# 08-RF_GPS.net
KiCad netlist of a schematic drawn in Altium Designer
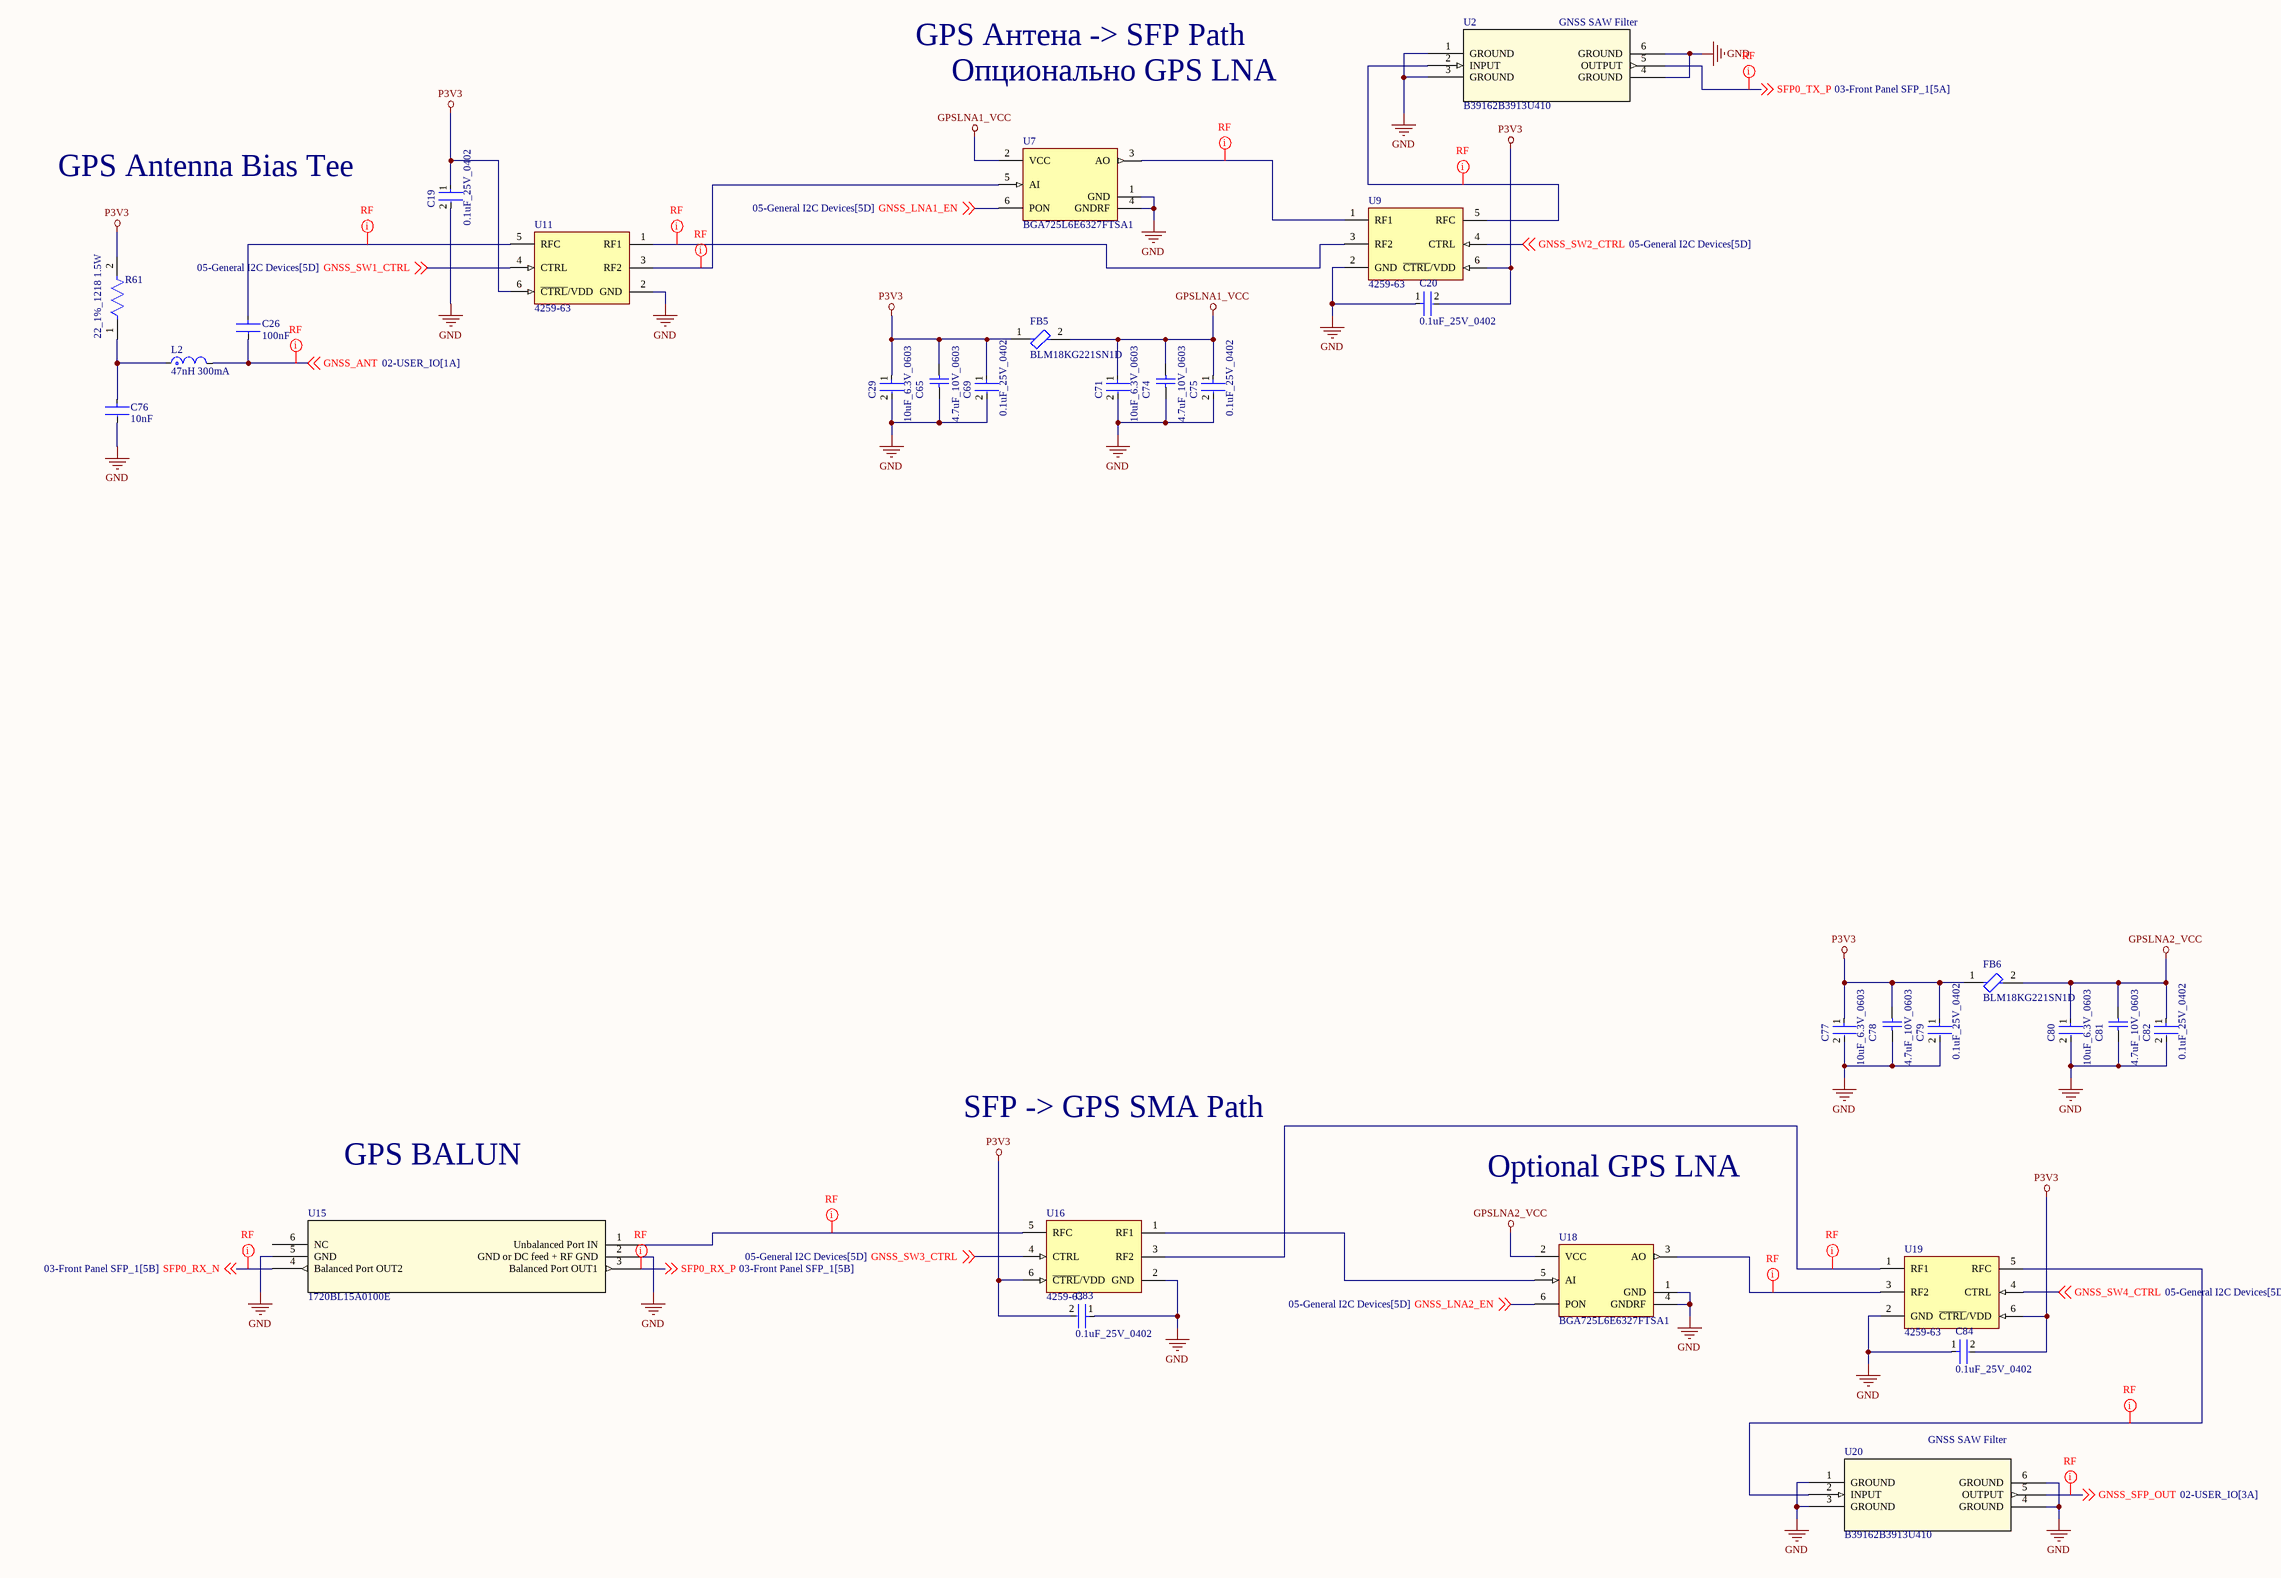
[diagram p0: 08-RF_GPS.SchDoc]

(export (version "E")
  (design (tool "Eeschema 10.0.6"))
  (components
    (comp (ref "C19")
      (value "0.1uF_25V_0402")
      (footprint "FP-0402-L_1_0_1-W_0_5_0_1-IPC_C")
      (description "General Purpose Ceramic Capacitor, 0402, 100nF, 10%, X7R, 15%, 25V")
      (fields (field (name "VOLTAGE") "25V") (field (name "TOLERANCE") "10%"))
      (libsource (lib "Altium Content Vault") (part "b4654b650e69147ec39a6b967a45e02"))
    )
    (comp (ref "C20")
      (value "0.1uF_25V_0402")
      (footprint "FP-0402-L_1_0_1-W_0_5_0_1-IPC_C")
      (description "General Purpose Ceramic Capacitor, 0402, 100nF, 10%, X7R, 15%, 25V")
      (fields (field (name "VOLTAGE") "25V") (field (name "TOLERANCE") "10%"))
      (libsource (lib "Altium Content Vault") (part "b4654b650e69147ec39a6b967a45e02"))
    )
    (comp (ref "C26")
      (value "100nF")
      (footprint "FP-0402-L_1_0_0_05-W_0_5-IPC_B")
      (description "None")
      (fields (field (name "TOLERANCE") "10%"))
      (libsource (lib "") (part "b4654b650e69147ec39a6b967a45e02_1"))
    )
    (comp (ref "C29")
      (value "10uF_6.3V_0603")
      (footprint "FP-C0603C106M9PACTU-MFG")
      (description "CAP CER 10UF 6.3V X5R 0603")
      (fields
        (field (name "MANUFACTURER PART NUMBER") "C0603C106M9PACTU")
        (field (name "MANUFACTURER") "Kemet")
      )
      (libsource (lib "Altium Content Vault") (part "b4654b650e69147ec39a6b967a45e02"))
    )
    (comp (ref "C65")
      (value "4.7uF_10V_0603")
      (footprint "CAPC1608X87X35NL15T15")
      (fields (field (name "PART NUMBER") "C0603C475K8PACTU") (field (name "MANUFACTURER") "Kemet"))
      (libsource (lib "Altium Content Vault") (part "CAP"))
    )
    (comp (ref "C69")
      (value "0.1uF_25V_0402")
      (footprint "FP-0402-L_1_0_1-W_0_5_0_1-IPC_C")
      (description "General Purpose Ceramic Capacitor, 0402, 100nF, 10%, X7R, 15%, 25V")
      (fields (field (name "VOLTAGE") "25V") (field (name "TOLERANCE") "10%"))
      (libsource (lib "Altium Content Vault") (part "b4654b650e69147ec39a6b967a45e02"))
    )
    (comp (ref "C71")
      (value "10uF_6.3V_0603")
      (footprint "FP-C0603C106M9PACTU-MFG")
      (description "CAP CER 10UF 6.3V X5R 0603")
      (fields
        (field (name "MANUFACTURER PART NUMBER") "C0603C106M9PACTU")
        (field (name "MANUFACTURER") "Kemet")
      )
      (libsource (lib "Altium Content Vault") (part "b4654b650e69147ec39a6b967a45e02"))
    )
    (comp (ref "C74")
      (value "4.7uF_10V_0603")
      (footprint "CAPC1608X87X35NL15T15")
      (fields (field (name "PART NUMBER") "C0603C475K8PACTU") (field (name "MANUFACTURER") "Kemet"))
      (libsource (lib "Altium Content Vault") (part "CAP"))
    )
    (comp (ref "C75")
      (value "0.1uF_25V_0402")
      (footprint "FP-0402-L_1_0_1-W_0_5_0_1-IPC_C")
      (description "General Purpose Ceramic Capacitor, 0402, 100nF, 10%, X7R, 15%, 25V")
      (fields (field (name "VOLTAGE") "25V") (field (name "TOLERANCE") "10%"))
      (libsource (lib "Altium Content Vault") (part "b4654b650e69147ec39a6b967a45e02"))
    )
    (comp (ref "C76")
      (value "10nF")
      (footprint "FP-GRM033-0_03-IPC_B")
      (description "Chip Multilayer Ceramic Capacitors for General Purpose, 0201, 10000pF, X7R, 15%, 10%, 16V")
      (fields (field (name "TOLERANCE") "10%"))
      (libsource (lib "") (part "b4654b650e69147ec39a6b967a45e02_1"))
    )
    (comp (ref "C77")
      (value "10uF_6.3V_0603")
      (footprint "FP-C0603C106M9PACTU-MFG")
      (description "CAP CER 10UF 6.3V X5R 0603")
      (fields
        (field (name "MANUFACTURER PART NUMBER") "C0603C106M9PACTU")
        (field (name "MANUFACTURER") "Kemet")
      )
      (libsource (lib "Altium Content Vault") (part "b4654b650e69147ec39a6b967a45e02"))
    )
    (comp (ref "C78")
      (value "4.7uF_10V_0603")
      (footprint "CAPC1608X87X35NL15T15")
      (fields (field (name "PART NUMBER") "C0603C475K8PACTU") (field (name "MANUFACTURER") "Kemet"))
      (libsource (lib "Altium Content Vault") (part "CAP"))
    )
    (comp (ref "C79")
      (value "0.1uF_25V_0402")
      (footprint "FP-0402-L_1_0_1-W_0_5_0_1-IPC_C")
      (description "General Purpose Ceramic Capacitor, 0402, 100nF, 10%, X7R, 15%, 25V")
      (fields (field (name "VOLTAGE") "25V") (field (name "TOLERANCE") "10%"))
      (libsource (lib "Altium Content Vault") (part "b4654b650e69147ec39a6b967a45e02"))
    )
    (comp (ref "C80")
      (value "10uF_6.3V_0603")
      (footprint "FP-C0603C106M9PACTU-MFG")
      (description "CAP CER 10UF 6.3V X5R 0603")
      (fields
        (field (name "MANUFACTURER PART NUMBER") "C0603C106M9PACTU")
        (field (name "MANUFACTURER") "Kemet")
      )
      (libsource (lib "Altium Content Vault") (part "b4654b650e69147ec39a6b967a45e02"))
    )
    (comp (ref "C81")
      (value "4.7uF_10V_0603")
      (footprint "CAPC1608X87X35NL15T15")
      (fields (field (name "PART NUMBER") "C0603C475K8PACTU") (field (name "MANUFACTURER") "Kemet"))
      (libsource (lib "Altium Content Vault") (part "CAP"))
    )
    (comp (ref "C82")
      (value "0.1uF_25V_0402")
      (footprint "FP-0402-L_1_0_1-W_0_5_0_1-IPC_C")
      (description "General Purpose Ceramic Capacitor, 0402, 100nF, 10%, X7R, 15%, 25V")
      (fields (field (name "VOLTAGE") "25V") (field (name "TOLERANCE") "10%"))
      (libsource (lib "Altium Content Vault") (part "b4654b650e69147ec39a6b967a45e02"))
    )
    (comp (ref "C83")
      (value "0.1uF_25V_0402")
      (footprint "FP-0402-L_1_0_1-W_0_5_0_1-IPC_C")
      (description "General Purpose Ceramic Capacitor, 0402, 100nF, 10%, X7R, 15%, 25V")
      (fields (field (name "VOLTAGE") "25V") (field (name "TOLERANCE") "10%"))
      (libsource (lib "Altium Content Vault") (part "b4654b650e69147ec39a6b967a45e02"))
    )
    (comp (ref "C84")
      (value "0.1uF_25V_0402")
      (footprint "FP-0402-L_1_0_1-W_0_5_0_1-IPC_C")
      (description "General Purpose Ceramic Capacitor, 0402, 100nF, 10%, X7R, 15%, 25V")
      (fields (field (name "VOLTAGE") "25V") (field (name "TOLERANCE") "10%"))
      (libsource (lib "Altium Content Vault") (part "b4654b650e69147ec39a6b967a45e02"))
    )
    (comp (ref "FB5")
      (value "BLM18KG221SN1D")
      (footprint "FP-BLM18-0_15-t0_8-IPC_B")
      (description "Chip Ferrite Bead, 0603, 220Ω @ 100MHz, 0.05Ω, 25%, 2.2A")
      (fields (field (name "TOLERANCE") "25%"))
      (libsource (lib "Altium Content Vault") (part "5f30dd21d616792df468990f7003faa"))
    )
    (comp (ref "FB6")
      (value "BLM18KG221SN1D")
      (footprint "FP-BLM18-0_15-t0_8-IPC_B")
      (description "Chip Ferrite Bead, 0603, 220Ω @ 100MHz, 0.05Ω, 25%, 2.2A")
      (fields (field (name "TOLERANCE") "25%"))
      (libsource (lib "Altium Content Vault") (part "5f30dd21d616792df468990f7003faa"))
    )
    (comp (ref "L2")
      (value "47nH 300mA")
      (footprint "FP-LQG15HH_02-IPC_B")
      (description "Multilayer type RF Inductor 47nH ±5% 0.72Ω 300mA 0402")
      (fields (field (name "TOLERANCE") "5%"))
      (libsource (lib "Altium Content Vault") (part "4cc4b267dca4c8e51f7102f422741d8"))
    )
    (comp (ref "R61")
      (value "22_1%_1218 1.5W")
      (footprint "FP-CRCW1218-HPe3-MFG")
      (description "RES Thick Film, 22.6Ω, 1%, 1.5W, 100ppm/°C, 1218")
      (fields (field (name "TOLERANCE") "1%"))
      (libsource (lib "Altium Content Vault") (part "1029c3af85768c4190bb7ad29bc67b5"))
    )
    (comp (ref "U2")
      (value "B39162B3913U410")
      (footprint "B39162B3913U410_QUA")
      (description "No Description Available")
      (libsource (lib "B39162B3913U410") (part "B39162B3913U410"))
    )
    (comp (ref "U7")
      (value "BGA725L6E6327FTSA1")
      (footprint "FP-PG-TSLP-6-MFG")
      (description "IC AMP GPS 1.55-1.615GHZ TSLP6-2")
      (fields
        (field (name "OCTOPART") "https://octopart.com/bga725l6e6327ftsa1-infineon-23421878")
        (field (name "MANUFACTURER") "Infineon")
      )
      (libsource (lib "Altium Content Vault") (part "3fcdeb0a4b0737d1798366062040e11"))
    )
    (comp (ref "U9")
      (value "4259-63")
      (footprint "PERE-SC-70-6_M")
      (description "IC RF Switch SPDT, 50 Ohm, 6-Pin SC70, RoHS, Tape and Reel")
      (fields (field (name "MANUFACTURER") "Peregrine Semiconductor"))
      (libsource (lib "Altium Content Vault") (part "PERE-PE4259-6"))
    )
    (comp (ref "U11")
      (value "4259-63")
      (footprint "PERE-SC-70-6_M")
      (description "IC RF Switch SPDT, 50 Ohm, 6-Pin SC70, RoHS, Tape and Reel")
      (fields (field (name "MANUFACTURER") "Peregrine Semiconductor"))
      (libsource (lib "") (part "PERE-PE4259-6_1"))
    )
    (comp (ref "U15")
      (value "1720BL15A0100E")
      (footprint "SMT_15B0050E_JOT")
      (description "No Description Available")
      (libsource (lib "1720BL15A0100E") (part "1720BL15A0100E"))
    )
    (comp (ref "U16")
      (value "4259-63")
      (footprint "PERE-SC-70-6_M")
      (description "IC RF Switch SPDT, 50 Ohm, 6-Pin SC70, RoHS, Tape and Reel")
      (fields (field (name "MANUFACTURER") "Peregrine Semiconductor"))
      (libsource (lib "") (part "PERE-PE4259-6_1"))
    )
    (comp (ref "U18")
      (value "BGA725L6E6327FTSA1")
      (footprint "FP-PG-TSLP-6-MFG")
      (description "IC AMP GPS 1.55-1.615GHZ TSLP6-2")
      (fields
        (field (name "OCTOPART") "https://octopart.com/bga725l6e6327ftsa1-infineon-23421878")
        (field (name "MANUFACTURER") "Infineon")
      )
      (libsource (lib "Altium Content Vault") (part "3fcdeb0a4b0737d1798366062040e11"))
    )
    (comp (ref "U19")
      (value "4259-63")
      (footprint "PERE-SC-70-6_M")
      (description "IC RF Switch SPDT, 50 Ohm, 6-Pin SC70, RoHS, Tape and Reel")
      (fields (field (name "MANUFACTURER") "Peregrine Semiconductor"))
      (libsource (lib "Altium Content Vault") (part "PERE-PE4259-6"))
    )
    (comp (ref "U20")
      (value "B39162B3913U410")
      (footprint "B39162B3913U410_QUA")
      (description "No Description Available")
      (libsource (lib "B39162B3913U410") (part "B39162B3913U410"))
    )
  )
  (nets
    (net (code "1") (name "GND") (class "Default")
      (node (ref "C19") (pin "2") (pinfunction "2_2") (pintype "passive"))
      (node (ref "C20") (pin "1") (pinfunction "1_1") (pintype "passive"))
      (node (ref "C29") (pin "2") (pinfunction "2_2") (pintype "passive"))
      (node (ref "C65") (pin "1") (pinfunction "1_1") (pintype "passive"))
      (node (ref "C69") (pin "2") (pinfunction "2_2") (pintype "passive"))
      (node (ref "C71") (pin "2") (pinfunction "2_2") (pintype "passive"))
      (node (ref "C74") (pin "1") (pinfunction "1_1") (pintype "passive"))
      (node (ref "C75") (pin "2") (pinfunction "2_2") (pintype "passive"))
      (node (ref "C76") (pin "2") (pinfunction "2_2") (pintype "passive"))
      (node (ref "C77") (pin "2") (pinfunction "2_2") (pintype "passive"))
      (node (ref "C78") (pin "1") (pinfunction "1_1") (pintype "passive"))
      (node (ref "C79") (pin "2") (pinfunction "2_2") (pintype "passive"))
      (node (ref "C80") (pin "2") (pinfunction "2_2") (pintype "passive"))
      (node (ref "C81") (pin "1") (pinfunction "1_1") (pintype "passive"))
      (node (ref "C82") (pin "2") (pinfunction "2_2") (pintype "passive"))
      (node (ref "C83") (pin "1") (pinfunction "1_1") (pintype "passive"))
      (node (ref "C84") (pin "1") (pinfunction "1_1") (pintype "passive"))
      (node (ref "U11") (pin "2") (pinfunction "GND_2") (pintype "power_in"))
      (node (ref "U15") (pin "2") (pinfunction "GND_or_DC_feed_+_RF_GND_2") (pintype "power_in"))
      (node (ref "U15") (pin "5") (pinfunction "GND_5") (pintype "power_in"))
      (node (ref "U16") (pin "2") (pinfunction "GND_2") (pintype "power_in"))
      (node (ref "U18") (pin "1") (pinfunction "GND_1") (pintype "power_in"))
      (node (ref "U18") (pin "4") (pinfunction "GNDRF_4") (pintype "power_in"))
      (node (ref "U19") (pin "2") (pinfunction "GND_2") (pintype "power_in"))
      (node (ref "U2") (pin "1") (pinfunction "GROUND_1") (pintype "power_in"))
      (node (ref "U2") (pin "3") (pinfunction "GROUND_3") (pintype "power_in"))
      (node (ref "U2") (pin "4") (pinfunction "GROUND_4") (pintype "power_in"))
      (node (ref "U2") (pin "6") (pinfunction "GROUND_6") (pintype "power_in"))
      (node (ref "U20") (pin "1") (pinfunction "GROUND_1") (pintype "power_in"))
      (node (ref "U20") (pin "3") (pinfunction "GROUND_3") (pintype "power_in"))
      (node (ref "U20") (pin "4") (pinfunction "GROUND_4") (pintype "power_in"))
      (node (ref "U20") (pin "6") (pinfunction "GROUND_6") (pintype "power_in"))
      (node (ref "U7") (pin "1") (pinfunction "GND_1") (pintype "power_in"))
      (node (ref "U7") (pin "4") (pinfunction "GNDRF_4") (pintype "power_in"))
      (node (ref "U9") (pin "2") (pinfunction "GND_2") (pintype "power_in"))
    )
    (net (code "2") (name "GNSS_ANT") (class "Default")
      (node (ref "C26") (pin "2") (pinfunction "2_2") (pintype "passive"))
      (node (ref "L2") (pin "2") (pinfunction "2_2") (pintype "passive"))
    )
    (net (code "3") (name "GNSS_LNA1_EN") (class "Default")
      (node (ref "U7") (pin "6") (pinfunction "PON_6") (pintype "power_in"))
    )
    (net (code "4") (name "GNSS_LNA2_EN") (class "Default")
      (node (ref "U18") (pin "6") (pinfunction "PON_6") (pintype "power_in"))
    )
    (net (code "5") (name "GNSS_SFP_OUT") (class "Default")
      (node (ref "U20") (pin "5") (pinfunction "OUTPUT_5") (pintype "output"))
    )
    (net (code "6") (name "GNSS_SW1_CTRL") (class "Default")
      (node (ref "U11") (pin "4") (pinfunction "CTRL_4") (pintype "input"))
    )
    (net (code "7") (name "GNSS_SW2_CTRL") (class "Default")
      (node (ref "U9") (pin "4") (pinfunction "CTRL_4") (pintype "input"))
    )
    (net (code "8") (name "GNSS_SW3_CTRL") (class "Default")
      (node (ref "U16") (pin "4") (pinfunction "CTRL_4") (pintype "input"))
    )
    (net (code "9") (name "GNSS_SW4_CTRL") (class "Default")
      (node (ref "U19") (pin "4") (pinfunction "CTRL_4") (pintype "input"))
    )
    (net (code "10") (name "GPSLNA1_VCC") (class "Default")
      (node (ref "C71") (pin "1") (pinfunction "1_1") (pintype "passive"))
      (node (ref "C74") (pin "2") (pinfunction "2_2") (pintype "passive"))
      (node (ref "C75") (pin "1") (pinfunction "1_1") (pintype "passive"))
      (node (ref "FB5") (pin "2") (pinfunction "2_2") (pintype "passive"))
      (node (ref "U7") (pin "2") (pinfunction "VCC_2") (pintype "power_in"))
    )
    (net (code "11") (name "GPSLNA2_VCC") (class "Default")
      (node (ref "C80") (pin "1") (pinfunction "1_1") (pintype "passive"))
      (node (ref "C81") (pin "2") (pinfunction "2_2") (pintype "passive"))
      (node (ref "C82") (pin "1") (pinfunction "1_1") (pintype "passive"))
      (node (ref "FB6") (pin "2") (pinfunction "2_2") (pintype "passive"))
      (node (ref "U18") (pin "2") (pinfunction "VCC_2") (pintype "power_in"))
    )
    (net (code "12") (name "Net-(C76-Pad1)") (class "Default")
      (node (ref "C76") (pin "1") (pinfunction "1_1") (pintype "passive"))
      (node (ref "L2") (pin "1") (pinfunction "1_1") (pintype "passive"))
      (node (ref "R61") (pin "1") (pinfunction "1_1") (pintype "passive"))
    )
    (net (code "13") (name "Net-(U2-INPUT)") (class "Default")
      (node (ref "U2") (pin "2") (pinfunction "INPUT_2") (pintype "input"))
      (node (ref "U9") (pin "5") (pinfunction "RFC_5") (pintype "passive"))
    )
    (net (code "14") (name "Net-(U7-AO)") (class "Default")
      (node (ref "U7") (pin "3") (pinfunction "AO_3") (pintype "output"))
      (node (ref "U9") (pin "1") (pinfunction "RF1_1") (pintype "passive"))
    )
    (net (code "15") (name "Net-(U11-RF1)") (class "Default")
      (node (ref "U11") (pin "1") (pinfunction "RF1_1") (pintype "passive"))
      (node (ref "U9") (pin "3") (pinfunction "RF2_3") (pintype "passive"))
    )
    (net (code "16") (name "Net-(U11-RF2)") (class "Default")
      (node (ref "U11") (pin "3") (pinfunction "RF2_3") (pintype "passive"))
      (node (ref "U7") (pin "5") (pinfunction "AI_5") (pintype "input"))
    )
    (net (code "17") (name "Net-(U11-RFC)") (class "Default")
      (node (ref "C26") (pin "1") (pinfunction "1_1") (pintype "passive"))
      (node (ref "U11") (pin "5") (pinfunction "RFC_5") (pintype "passive"))
    )
    (net (code "18") (name "Net-(U15-Unbalanced_Port_IN)") (class "Default")
      (node (ref "U15") (pin "1") (pinfunction "Unbalanced_Port_IN_1") (pintype "passive"))
      (node (ref "U16") (pin "5") (pinfunction "RFC_5") (pintype "passive"))
    )
    (net (code "19") (name "Net-(U16-RF1)") (class "Default")
      (node (ref "U16") (pin "1") (pinfunction "RF1_1") (pintype "passive"))
      (node (ref "U18") (pin "5") (pinfunction "AI_5") (pintype "input"))
    )
    (net (code "20") (name "Net-(U16-RF2)") (class "Default")
      (node (ref "U16") (pin "3") (pinfunction "RF2_3") (pintype "passive"))
      (node (ref "U19") (pin "1") (pinfunction "RF1_1") (pintype "passive"))
    )
    (net (code "21") (name "Net-(U18-AO)") (class "Default")
      (node (ref "U18") (pin "3") (pinfunction "AO_3") (pintype "output"))
      (node (ref "U19") (pin "3") (pinfunction "RF2_3") (pintype "passive"))
    )
    (net (code "22") (name "Net-(U19-RFC)") (class "Default")
      (node (ref "U19") (pin "5") (pinfunction "RFC_5") (pintype "passive"))
      (node (ref "U20") (pin "2") (pinfunction "INPUT_2") (pintype "input"))
    )
    (net (code "23") (name "P3V3") (class "Default")
      (node (ref "C19") (pin "1") (pinfunction "1_1") (pintype "passive"))
      (node (ref "C20") (pin "2") (pinfunction "2_2") (pintype "passive"))
      (node (ref "C29") (pin "1") (pinfunction "1_1") (pintype "passive"))
      (node (ref "C65") (pin "2") (pinfunction "2_2") (pintype "passive"))
      (node (ref "C69") (pin "1") (pinfunction "1_1") (pintype "passive"))
      (node (ref "C77") (pin "1") (pinfunction "1_1") (pintype "passive"))
      (node (ref "C78") (pin "2") (pinfunction "2_2") (pintype "passive"))
      (node (ref "C79") (pin "1") (pinfunction "1_1") (pintype "passive"))
      (node (ref "C83") (pin "2") (pinfunction "2_2") (pintype "passive"))
      (node (ref "C84") (pin "2") (pinfunction "2_2") (pintype "passive"))
      (node (ref "FB5") (pin "1") (pinfunction "1_1") (pintype "passive"))
      (node (ref "FB6") (pin "1") (pinfunction "1_1") (pintype "passive"))
      (node (ref "R61") (pin "2") (pinfunction "2_2") (pintype "passive"))
      (node (ref "U11") (pin "6") (pinfunction "~{CTRL}/VDD_6") (pintype "input"))
      (node (ref "U16") (pin "6") (pinfunction "~{CTRL}/VDD_6") (pintype "input"))
      (node (ref "U19") (pin "6") (pinfunction "~{CTRL}/VDD_6") (pintype "input"))
      (node (ref "U9") (pin "6") (pinfunction "~{CTRL}/VDD_6") (pintype "input"))
    )
    (net (code "24") (name "SFP0_RX_N") (class "Default")
      (node (ref "U15") (pin "4") (pinfunction "Balanced_Port_OUT2_4") (pintype "output"))
    )
    (net (code "25") (name "SFP0_RX_P") (class "Default")
      (node (ref "U15") (pin "3") (pinfunction "Balanced_Port_OUT1_3") (pintype "output"))
    )
    (net (code "26") (name "SFP0_TX_P") (class "Default")
      (node (ref "U2") (pin "5") (pinfunction "OUTPUT_5") (pintype "output"))
    )
    (net (code "27") (name "unconnected-(U15-NC-Pad6)") (class "Default")
      (node (ref "U15") (pin "6") (pinfunction "NC_6") (pintype "passive"))
    )
  )
)
